# holo_clock.net
KiCad netlist of a schematic drawn in EAGLE
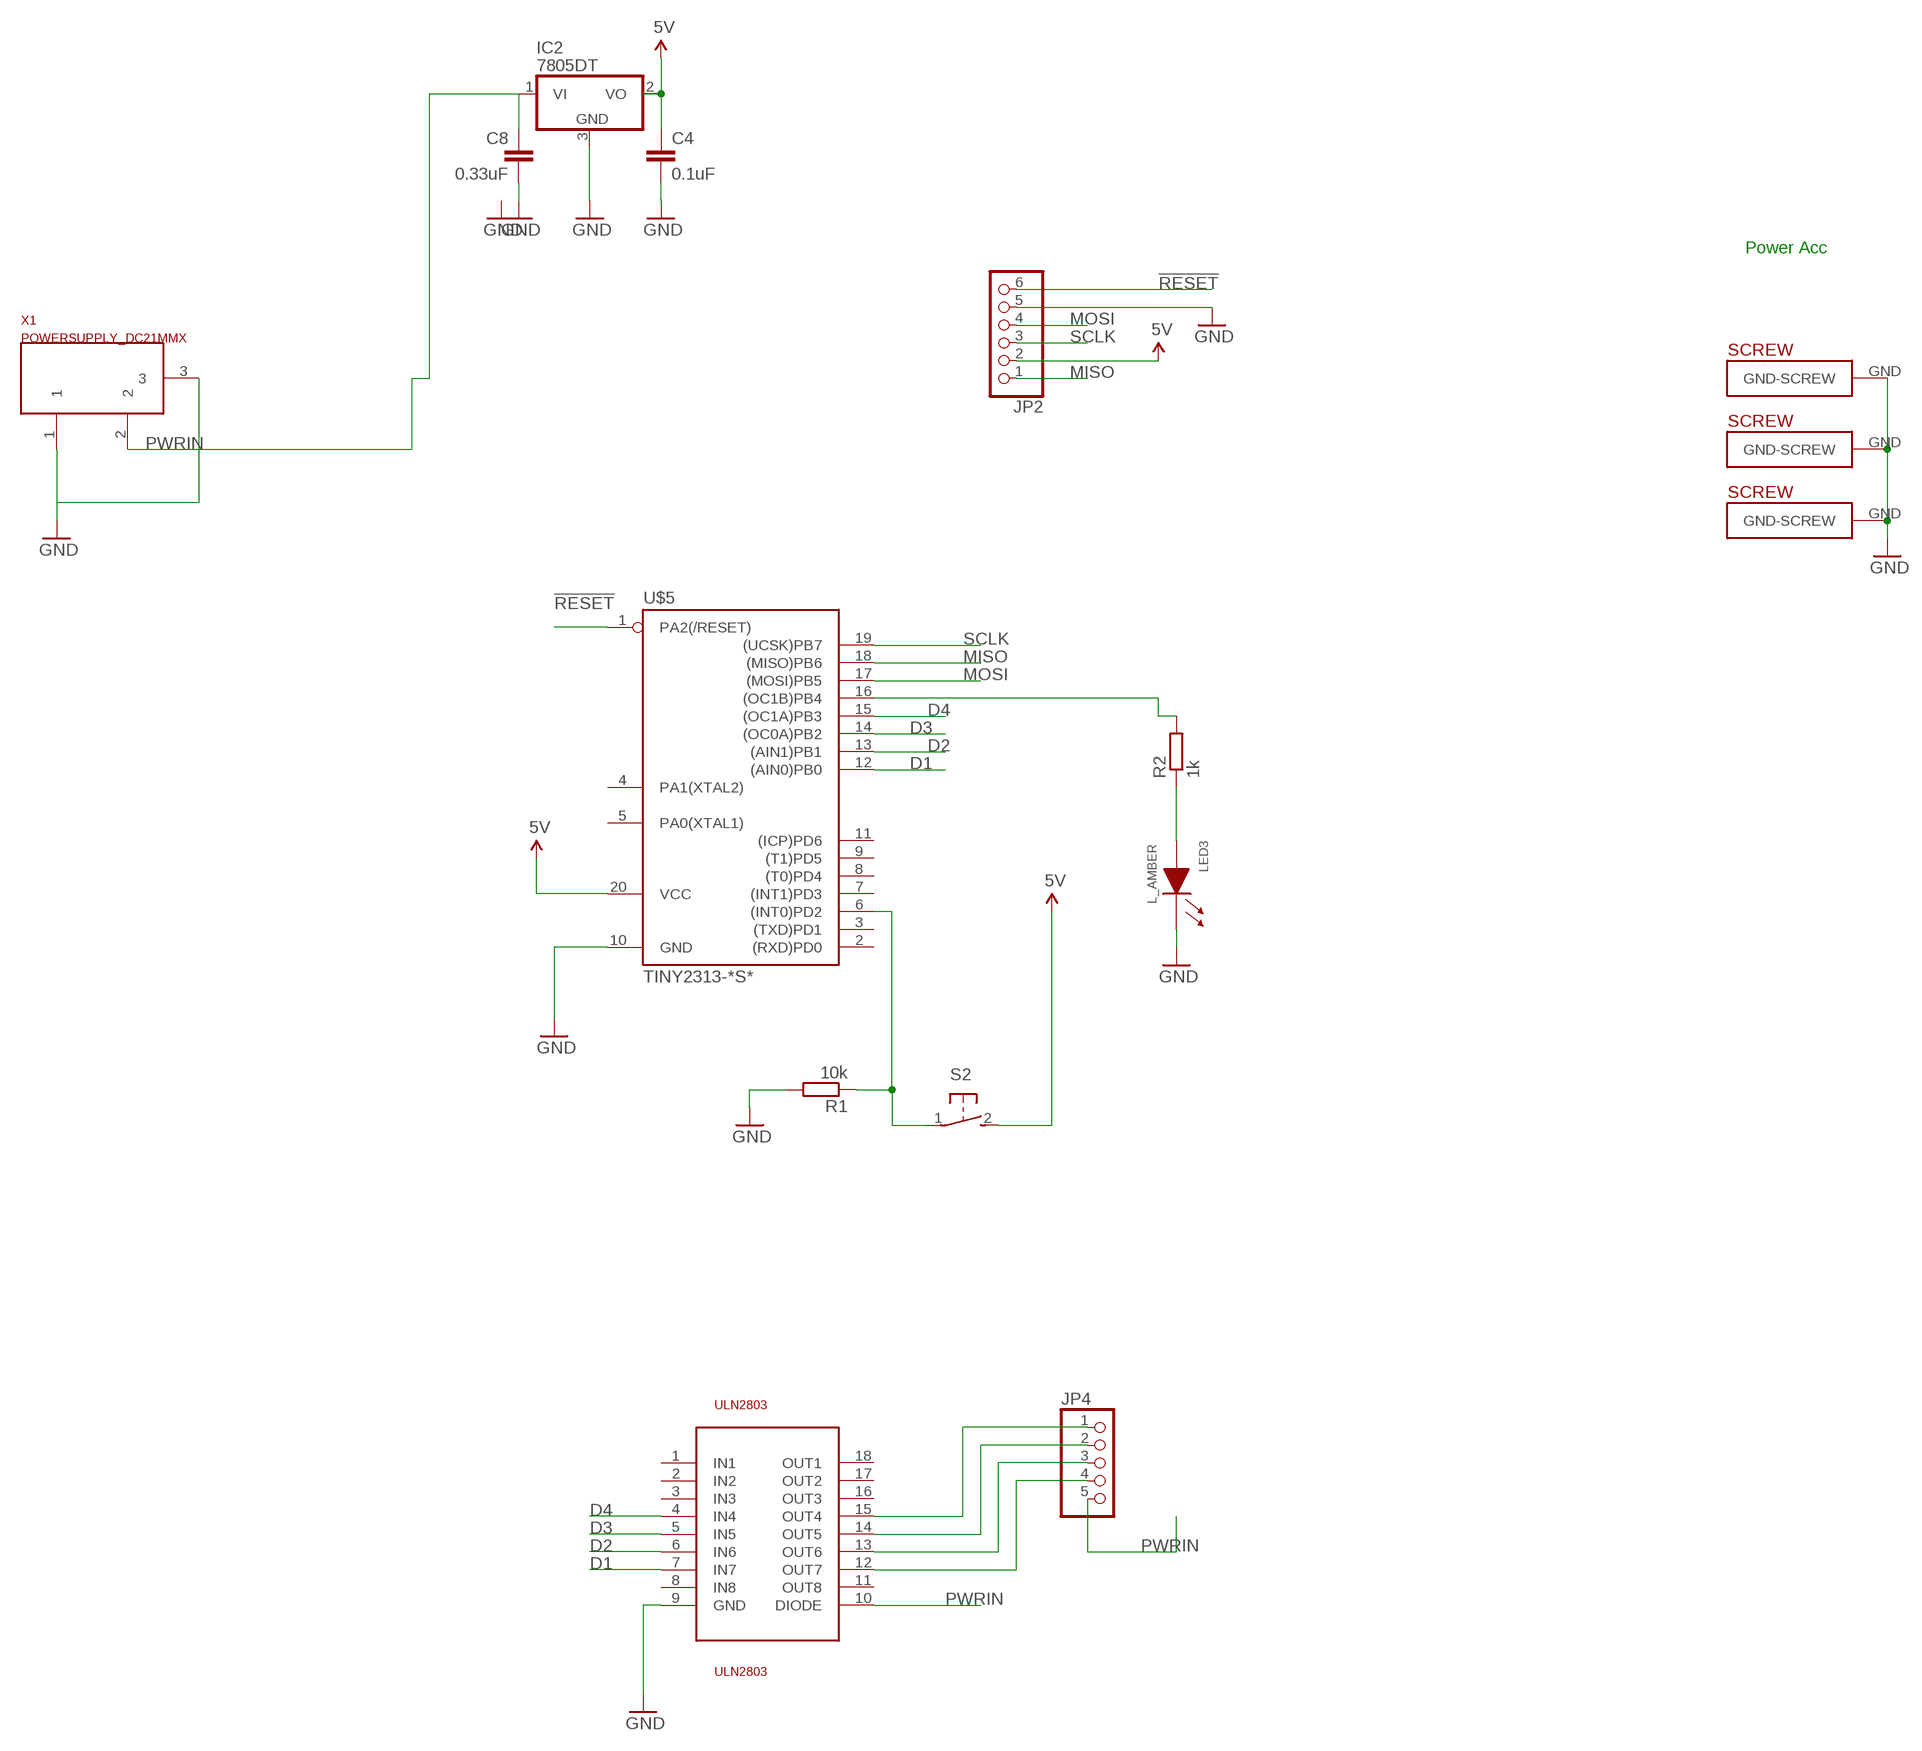
[diagram p0: schematic, sheet 1]

(export (version "E")
  (design (tool "Eeschema 10.0.6"))
  (components
    (comp (ref "C4")
      (value "0.1uF")
      (footprint "eagle-import:CAP-PTH-SMALL2")
      (libsource (lib "eagle-import") (part "CAPPTH2"))
    )
    (comp (ref "C8")
      (value "0.33uF")
      (footprint "eagle-import:CAP-PTH-SMALL2")
      (libsource (lib "eagle-import") (part "CAPPTH2"))
    )
    (comp (ref "IC2")
      (value "7805DT")
      (footprint "eagle-import:TO252")
      (libsource (lib "eagle-import") (part "78DT05"))
    )
    (comp (ref "JP2")
      (value "PINHD-1X6")
      (footprint "eagle-import:1X06")
      (libsource (lib "eagle-import") (part "PINHD-1X6"))
    )
    (comp (ref "JP4")
      (value "PINHD-1X5")
      (footprint "eagle-import:1X05")
      (libsource (lib "eagle-import") (part "PINHD-1X5"))
    )
    (comp (ref "LED3")
      (value "L_AMBER")
      (footprint "eagle-import:LED0805")
      (libsource (lib "eagle-import") (part "LED0805"))
    )
    (comp (ref "R1")
      (value "10k")
      (footprint "eagle-import:R0805")
      (libsource (lib "eagle-import") (part "R-EU_R0805"))
    )
    (comp (ref "R2")
      (value "1k")
      (footprint "eagle-import:R0805")
      (libsource (lib "eagle-import") (part "R-EU_R0805"))
    )
    (comp (ref "S2")
      (value "31-XX")
      (footprint "eagle-import:B3F-31XX")
      (fields (field (name "MPN") "B3F-3100"))
      (libsource (lib "eagle-import") (part "31-XX"))
    )
    (comp (ref "U$5")
      (value "TINY2313-*S*")
      (footprint "eagle-import:SO20L$")
      (libsource (lib "eagle-import") (part "TINY2313-S"))
    )
    (comp (ref "U$14")
      (value "PLATED-SCREW")
      (footprint "eagle-import:PLATEDSCREW")
      (libsource (lib "eagle-import") (part "PLATED-SCREW"))
    )
    (comp (ref "U$17")
      (value "PLATED-SCREW")
      (footprint "eagle-import:PLATEDSCREW")
      (libsource (lib "eagle-import") (part "PLATED-SCREW"))
    )
    (comp (ref "U$18")
      (value "PLATED-SCREW")
      (footprint "eagle-import:PLATEDSCREW")
      (libsource (lib "eagle-import") (part "PLATED-SCREW"))
    )
    (comp (ref "ULN2803")
      (value "ULN2803")
      (footprint "eagle-import:SO18L")
      (libsource (lib "eagle-import") (part "ULN2803"))
    )
    (comp (ref "X1")
      (value "POWERSUPPLY_DC21MMX")
      (footprint "eagle-import:POWERSUPPLY_DC-21MM")
      (libsource (lib "eagle-import") (part "POWERSUPPLY_DC21MMX"))
    )
  )
  (nets
    (net (code "1") (name "/D1") (class "Default")
      (node (ref "U$5") (pin "12") (pinfunction "(AIN0)PB0_12") (pintype "bidirectional"))
      (node (ref "ULN2803") (pin "7") (pinfunction "IN7_7") (pintype "input"))
    )
    (net (code "2") (name "/D2") (class "Default")
      (node (ref "U$5") (pin "13") (pinfunction "(AIN1)PB1_13") (pintype "bidirectional"))
      (node (ref "ULN2803") (pin "6") (pinfunction "IN6_6") (pintype "input"))
    )
    (net (code "3") (name "/D3") (class "Default")
      (node (ref "U$5") (pin "14") (pinfunction "(OC0A)PB2_14") (pintype "bidirectional"))
      (node (ref "ULN2803") (pin "5") (pinfunction "IN5_5") (pintype "input"))
    )
    (net (code "4") (name "/D4") (class "Default")
      (node (ref "U$5") (pin "15") (pinfunction "(OC1A)PB3_15") (pintype "bidirectional"))
      (node (ref "ULN2803") (pin "4") (pinfunction "IN4_4") (pintype "input"))
    )
    (net (code "5") (name "/MISO") (class "Default")
      (node (ref "JP2") (pin "1") (pinfunction "1_1") (pintype "passive"))
      (node (ref "U$5") (pin "18") (pinfunction "(MISO)PB6_18") (pintype "bidirectional"))
    )
    (net (code "6") (name "/MOSI") (class "Default")
      (node (ref "JP2") (pin "4") (pinfunction "4_4") (pintype "passive"))
      (node (ref "U$5") (pin "17") (pinfunction "(MOSI)PB5_17") (pintype "bidirectional"))
    )
    (net (code "7") (name "/PWRIN") (class "Default")
      (node (ref "C8") (pin "1") (pinfunction "1_1") (pintype "passive"))
      (node (ref "IC2") (pin "1") (pinfunction "VI_1") (pintype "input"))
      (node (ref "JP4") (pin "5") (pinfunction "5_5") (pintype "passive"))
      (node (ref "ULN2803") (pin "10") (pinfunction "DIODE_10") (pintype "power_in"))
      (node (ref "X1") (pin "2") (pinfunction "2_2") (pintype "power_in"))
    )
    (net (code "8") (name "/SCLK") (class "Default")
      (node (ref "JP2") (pin "3") (pinfunction "3_3") (pintype "passive"))
      (node (ref "U$5") (pin "19") (pinfunction "(UCSK)PB7_19") (pintype "bidirectional"))
    )
    (net (code "9") (name "/~{RESET}") (class "Default")
      (node (ref "JP2") (pin "6") (pinfunction "6_6") (pintype "passive"))
      (node (ref "U$5") (pin "1") (pinfunction "PA2(/RESET)_1") (pintype "input"))
    )
    (net (code "10") (name "5V") (class "Default")
      (node (ref "C4") (pin "1") (pinfunction "1_1") (pintype "passive"))
      (node (ref "IC2") (pin "2") (pinfunction "VO_2") (pintype "passive"))
      (node (ref "JP2") (pin "2") (pinfunction "2_2") (pintype "passive"))
      (node (ref "S2") (pin "2") (pinfunction "S_2") (pintype "passive"))
      (node (ref "U$5") (pin "20") (pinfunction "VCC_20") (pintype "power_in"))
    )
    (net (code "11") (name "GND") (class "Default")
      (node (ref "C4") (pin "2") (pinfunction "2_2") (pintype "passive"))
      (node (ref "C8") (pin "2") (pinfunction "2_2") (pintype "passive"))
      (node (ref "IC2") (pin "3") (pinfunction "GND_3") (pintype "passive"))
      (node (ref "JP2") (pin "5") (pinfunction "5_5") (pintype "passive"))
      (node (ref "LED3") (pin "1") (pinfunction "CA_1") (pintype "passive"))
      (node (ref "R1") (pin "2") (pinfunction "2_2") (pintype "passive"))
      (node (ref "U$14") (pin "GND") (pinfunction "GND-SCREW_GND") (pintype "bidirectional"))
      (node (ref "U$17") (pin "GND") (pinfunction "GND-SCREW_GND") (pintype "bidirectional"))
      (node (ref "U$18") (pin "GND") (pinfunction "GND-SCREW_GND") (pintype "bidirectional"))
      (node (ref "U$5") (pin "10") (pinfunction "GND_10") (pintype "power_in"))
      (node (ref "ULN2803") (pin "9") (pinfunction "GND_9") (pintype "power_in"))
      (node (ref "X1") (pin "1") (pinfunction "1_1") (pintype "power_in"))
      (node (ref "X1") (pin "3") (pinfunction "3_3") (pintype "power_in"))
    )
    (net (code "12") (name "Net-(LED3-AN)") (class "Default")
      (node (ref "LED3") (pin "2") (pinfunction "AN_2") (pintype "passive"))
      (node (ref "R2") (pin "1") (pinfunction "1_1") (pintype "passive"))
    )
    (net (code "13") (name "Net-(S2-P)") (class "Default")
      (node (ref "R1") (pin "1") (pinfunction "1_1") (pintype "passive"))
      (node (ref "S2") (pin "1") (pinfunction "P_1") (pintype "passive"))
      (node (ref "U$5") (pin "6") (pinfunction "(INT0)PD2_6") (pintype "bidirectional"))
    )
    (net (code "14") (name "Net-(U$5-(OC1B)PB4)") (class "Default")
      (node (ref "R2") (pin "2") (pinfunction "2_2") (pintype "passive"))
      (node (ref "U$5") (pin "16") (pinfunction "(OC1B)PB4_16") (pintype "bidirectional"))
    )
    (net (code "15") (name "Net-(ULN2803-OUT4)") (class "Default")
      (node (ref "JP4") (pin "1") (pinfunction "1_1") (pintype "passive"))
      (node (ref "ULN2803") (pin "15") (pinfunction "OUT4_15") (pintype "open_collector"))
    )
    (net (code "16") (name "Net-(ULN2803-OUT5)") (class "Default")
      (node (ref "JP4") (pin "2") (pinfunction "2_2") (pintype "passive"))
      (node (ref "ULN2803") (pin "14") (pinfunction "OUT5_14") (pintype "open_collector"))
    )
    (net (code "17") (name "Net-(ULN2803-OUT6)") (class "Default")
      (node (ref "JP4") (pin "3") (pinfunction "3_3") (pintype "passive"))
      (node (ref "ULN2803") (pin "13") (pinfunction "OUT6_13") (pintype "open_collector"))
    )
    (net (code "18") (name "Net-(ULN2803-OUT7)") (class "Default")
      (node (ref "JP4") (pin "4") (pinfunction "4_4") (pintype "passive"))
      (node (ref "ULN2803") (pin "12") (pinfunction "OUT7_12") (pintype "open_collector"))
    )
    (net (code "19") (name "unconnected-(U$5-(ICP)PD6-Pad11)") (class "Default")
      (node (ref "U$5") (pin "11") (pinfunction "(ICP)PD6_11") (pintype "bidirectional"))
    )
    (net (code "20") (name "unconnected-(U$5-(INT1)PD3-Pad7)") (class "Default")
      (node (ref "U$5") (pin "7") (pinfunction "(INT1)PD3_7") (pintype "bidirectional"))
    )
    (net (code "21") (name "unconnected-(U$5-(RXD)PD0-Pad2)") (class "Default")
      (node (ref "U$5") (pin "2") (pinfunction "(RXD)PD0_2") (pintype "bidirectional"))
    )
    (net (code "22") (name "unconnected-(U$5-(T0)PD4-Pad8)") (class "Default")
      (node (ref "U$5") (pin "8") (pinfunction "(T0)PD4_8") (pintype "bidirectional"))
    )
    (net (code "23") (name "unconnected-(U$5-(T1)PD5-Pad9)") (class "Default")
      (node (ref "U$5") (pin "9") (pinfunction "(T1)PD5_9") (pintype "bidirectional"))
    )
    (net (code "24") (name "unconnected-(U$5-(TXD)PD1-Pad3)") (class "Default")
      (node (ref "U$5") (pin "3") (pinfunction "(TXD)PD1_3") (pintype "bidirectional"))
    )
    (net (code "25") (name "unconnected-(U$5-PA0(XTAL1)-Pad5)") (class "Default")
      (node (ref "U$5") (pin "5") (pinfunction "PA0(XTAL1)_5") (pintype "bidirectional"))
    )
    (net (code "26") (name "unconnected-(U$5-PA1(XTAL2)-Pad4)") (class "Default")
      (node (ref "U$5") (pin "4") (pinfunction "PA1(XTAL2)_4") (pintype "bidirectional"))
    )
    (net (code "27") (name "unconnected-(ULN2803-IN1-Pad1)") (class "Default")
      (node (ref "ULN2803") (pin "1") (pinfunction "IN1_1") (pintype "input"))
    )
    (net (code "28") (name "unconnected-(ULN2803-IN2-Pad2)") (class "Default")
      (node (ref "ULN2803") (pin "2") (pinfunction "IN2_2") (pintype "input"))
    )
    (net (code "29") (name "unconnected-(ULN2803-IN3-Pad3)") (class "Default")
      (node (ref "ULN2803") (pin "3") (pinfunction "IN3_3") (pintype "input"))
    )
    (net (code "30") (name "unconnected-(ULN2803-IN8-Pad8)") (class "Default")
      (node (ref "ULN2803") (pin "8") (pinfunction "IN8_8") (pintype "input"))
    )
    (net (code "31") (name "unconnected-(ULN2803-OUT1-Pad18)") (class "Default")
      (node (ref "ULN2803") (pin "18") (pinfunction "OUT1_18") (pintype "open_collector"))
    )
    (net (code "32") (name "unconnected-(ULN2803-OUT2-Pad17)") (class "Default")
      (node (ref "ULN2803") (pin "17") (pinfunction "OUT2_17") (pintype "open_collector"))
    )
    (net (code "33") (name "unconnected-(ULN2803-OUT3-Pad16)") (class "Default")
      (node (ref "ULN2803") (pin "16") (pinfunction "OUT3_16") (pintype "open_collector"))
    )
    (net (code "34") (name "unconnected-(ULN2803-OUT8-Pad11)") (class "Default")
      (node (ref "ULN2803") (pin "11") (pinfunction "OUT8_11") (pintype "open_collector"))
    )
  )
)
